# EIS_Inverting_Adapter.net
KiCad netlist of a schematic drawn in Altium Designer
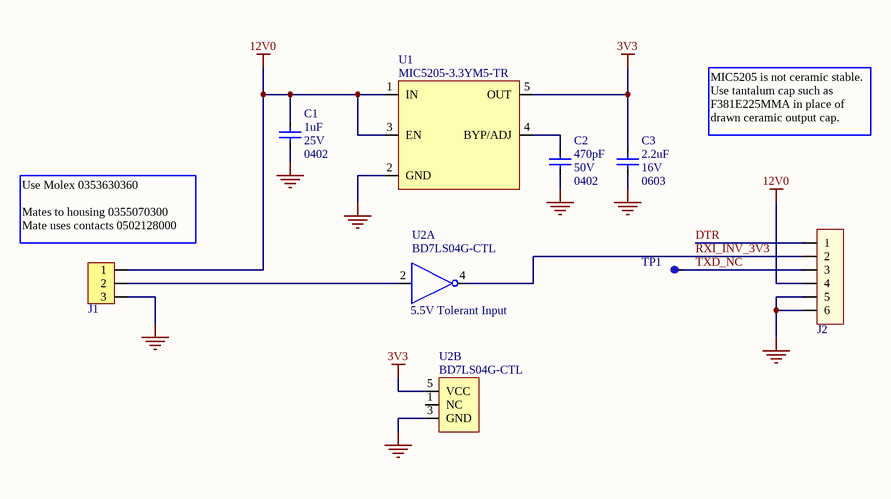
[diagram p0: EIS_Inverting_Adapter.SchDoc]

(export (version "E")
  (design (tool "Eeschema 10.0.6"))
  (components
    (comp (ref "C1")
      (value "E-GCA-0060")
      (footprint "CAPC1005X55N")
      (description "CAP GENERIC, CER, 1uF, 25V, 10%, X5R, 0402i/1005m")
      (fields
        (field (name "IMPERIAL SIZE") "0402")
        (field (name "CAPACITANCE") "1uF")
        (field (name "VOLTAGE") "25V")
        (field (name "TOLERANCE") "±10%")
        (field (name "MANUFACTURER PART NUMBER") "GENERIC")
      )
      (libsource (lib "Square Altium Server") (part "CAP NP"))
    )
    (comp (ref "C2")
      (value "E-CAP-0253")
      (footprint "CAPC1005X55N")
      (description "CAP, CER, 470pF, 50V, 5%, X7R, 0402 (1005m)")
      (fields
        (field (name "IMPERIAL SIZE") "0402")
        (field (name "CAPACITANCE") "470pF")
        (field (name "VOLTAGE") "50V")
        (field (name "TOLERANCE") "±5%")
        (field (name "MANUFACTURER") "Murata Electronics North America")
      )
      (libsource (lib "Square Altium Server") (part "CAP NP"))
    )
    (comp (ref "C3")
      (value "E-CAP-0056")
      (footprint "CAPC1608X90L")
      (description "CAP CER 2.2UF 16V 10% X5R 0603 (1608m)")
      (fields
        (field (name "IMPERIAL SIZE") "0603")
        (field (name "CAPACITANCE") "2.2uF")
        (field (name "VOLTAGE") "16V")
        (field (name "TOLERANCE") "10%")
        (field (name "MANUFACTURER") "Murata Electronics North America")
      )
      (libsource (lib "Square Altium Server") (part "CAP NP"))
    )
    (comp (ref "J1")
      (value "E-CON-0138")
      (footprint "SKT2P54_2P41X8X8P51_03")
      (description "CONN RCPT .100\" 3POS SNGL GOLD")
      (fields
        (field (name "MANUFACTURER PART NUMBER") "SSW-103-01-S-S")
        (field (name "MANUFACTURER") "Samtec Inc")
      )
      (libsource (lib "Square Altium Server") (part "CONN 3P HEADER"))
    )
    (comp (ref "J2")
      (value "E-CON-0064")
      (footprint "SIP508W63P254L1524H1041Q6")
      (description "CONN HEADER VERT 6POS .100 TIN")
      (fields
        (field (name "MANUFACTURER PART NUMBER") "640452-6")
        (field (name "MANUFACTURER") "TE Connectivity AMP Connectors")
      )
      (libsource (lib "Square Altium Server") (part "CONN 6P HEADER"))
    )
    (comp (ref "TP1")
      (value "MFG-0037")
      (footprint "TP_1.2mm_PAD_NOSILK")
      (description "Test Point - SM, 1.2mm")
      (libsource (lib "Square Altium Server") (part "TEST_POINT_SM_PAD"))
    )
    (comp (ref "U1")
      (value "MIC5205")
      (footprint "SOT95P280X145-5N")
      (description "Linear Voltage Regulator IC Positive Fixed 1 Output 150mA SOT-23-5")
      (fields (field (name "MANUFACTURER PART NUMBER 1") "MIC5205-3.3YM5-TR"))
      (libsource (lib "ics") (part "MIC5205"))
    )
    (comp (ref "U2")
      (value "5.5V Tolerant Input")
      (footprint "SOT95P280X125-5N")
      (description "Automotive Single Inverter")
      (fields (field (name "MANUFACTURER PART NUMBER 1") "BD7LS04G-CTL"))
      (libsource (lib "ics") (part "BD7LS04G-CTL"))
    )
  )
  (nets
    (net (code "1") (name "/DTR") (class "Default")
      (node (ref "J2") (pin "1") (pinfunction "1_1") (pintype "passive"))
    )
    (net (code "2") (name "/RXI_INV_3V3") (class "Default")
      (node (ref "J2") (pin "2") (pinfunction "2_2") (pintype "passive"))
      (node (ref "U2") (pin "4") (pinfunction "Y_4") (pintype "passive"))
    )
    (net (code "3") (name "/TXD_NC") (class "Default")
      (node (ref "J2") (pin "3") (pinfunction "3_3") (pintype "passive"))
      (node (ref "TP1") (pin "1") (pinfunction "1_1") (pintype "passive"))
    )
    (net (code "4") (name "3V3") (class "Default")
      (node (ref "C3") (pin "1") (pinfunction "1_1") (pintype "passive"))
      (node (ref "U1") (pin "5") (pinfunction "OUT_5") (pintype "passive"))
      (node (ref "U2") (pin "5") (pinfunction "VCC_5") (pintype "passive"))
    )
    (net (code "5") (name "12V0") (class "Default")
      (node (ref "C1") (pin "1") (pinfunction "1_1") (pintype "passive"))
      (node (ref "J1") (pin "1") (pinfunction "1_1") (pintype "passive"))
      (node (ref "J2") (pin "4") (pinfunction "4_4") (pintype "passive"))
      (node (ref "U1") (pin "1") (pinfunction "IN_1") (pintype "passive"))
      (node (ref "U1") (pin "3") (pinfunction "EN_3") (pintype "passive"))
    )
    (net (code "6") (name "GND") (class "Default")
      (node (ref "C1") (pin "2") (pinfunction "2_2") (pintype "passive"))
      (node (ref "C2") (pin "2") (pinfunction "2_2") (pintype "passive"))
      (node (ref "C3") (pin "2") (pinfunction "2_2") (pintype "passive"))
      (node (ref "J1") (pin "3") (pinfunction "3_3") (pintype "passive"))
      (node (ref "J2") (pin "5") (pinfunction "5_5") (pintype "passive"))
      (node (ref "J2") (pin "6") (pinfunction "6_6") (pintype "passive"))
      (node (ref "U1") (pin "2") (pinfunction "GND_2") (pintype "passive"))
      (node (ref "U2") (pin "3") (pinfunction "GND_3") (pintype "passive"))
    )
    (net (code "7") (name "Net-(U1-BYP{slash}ADJ)") (class "Default")
      (node (ref "C2") (pin "1") (pinfunction "1_1") (pintype "passive"))
      (node (ref "U1") (pin "4") (pinfunction "BYP/ADJ_4") (pintype "passive"))
    )
    (net (code "8") (name "Net-(U2A-A)") (class "Default")
      (node (ref "J1") (pin "2") (pinfunction "2_2") (pintype "passive"))
      (node (ref "U2") (pin "2") (pinfunction "A_2") (pintype "passive"))
    )
    (net (code "9") (name "unconnected-(U2B-NC-Pad1)") (class "Default")
      (node (ref "U2") (pin "1") (pinfunction "NC_1") (pintype "passive"))
    )
  )
)
